# Relay_Drivers.net
KiCad netlist of a schematic drawn in EAGLE
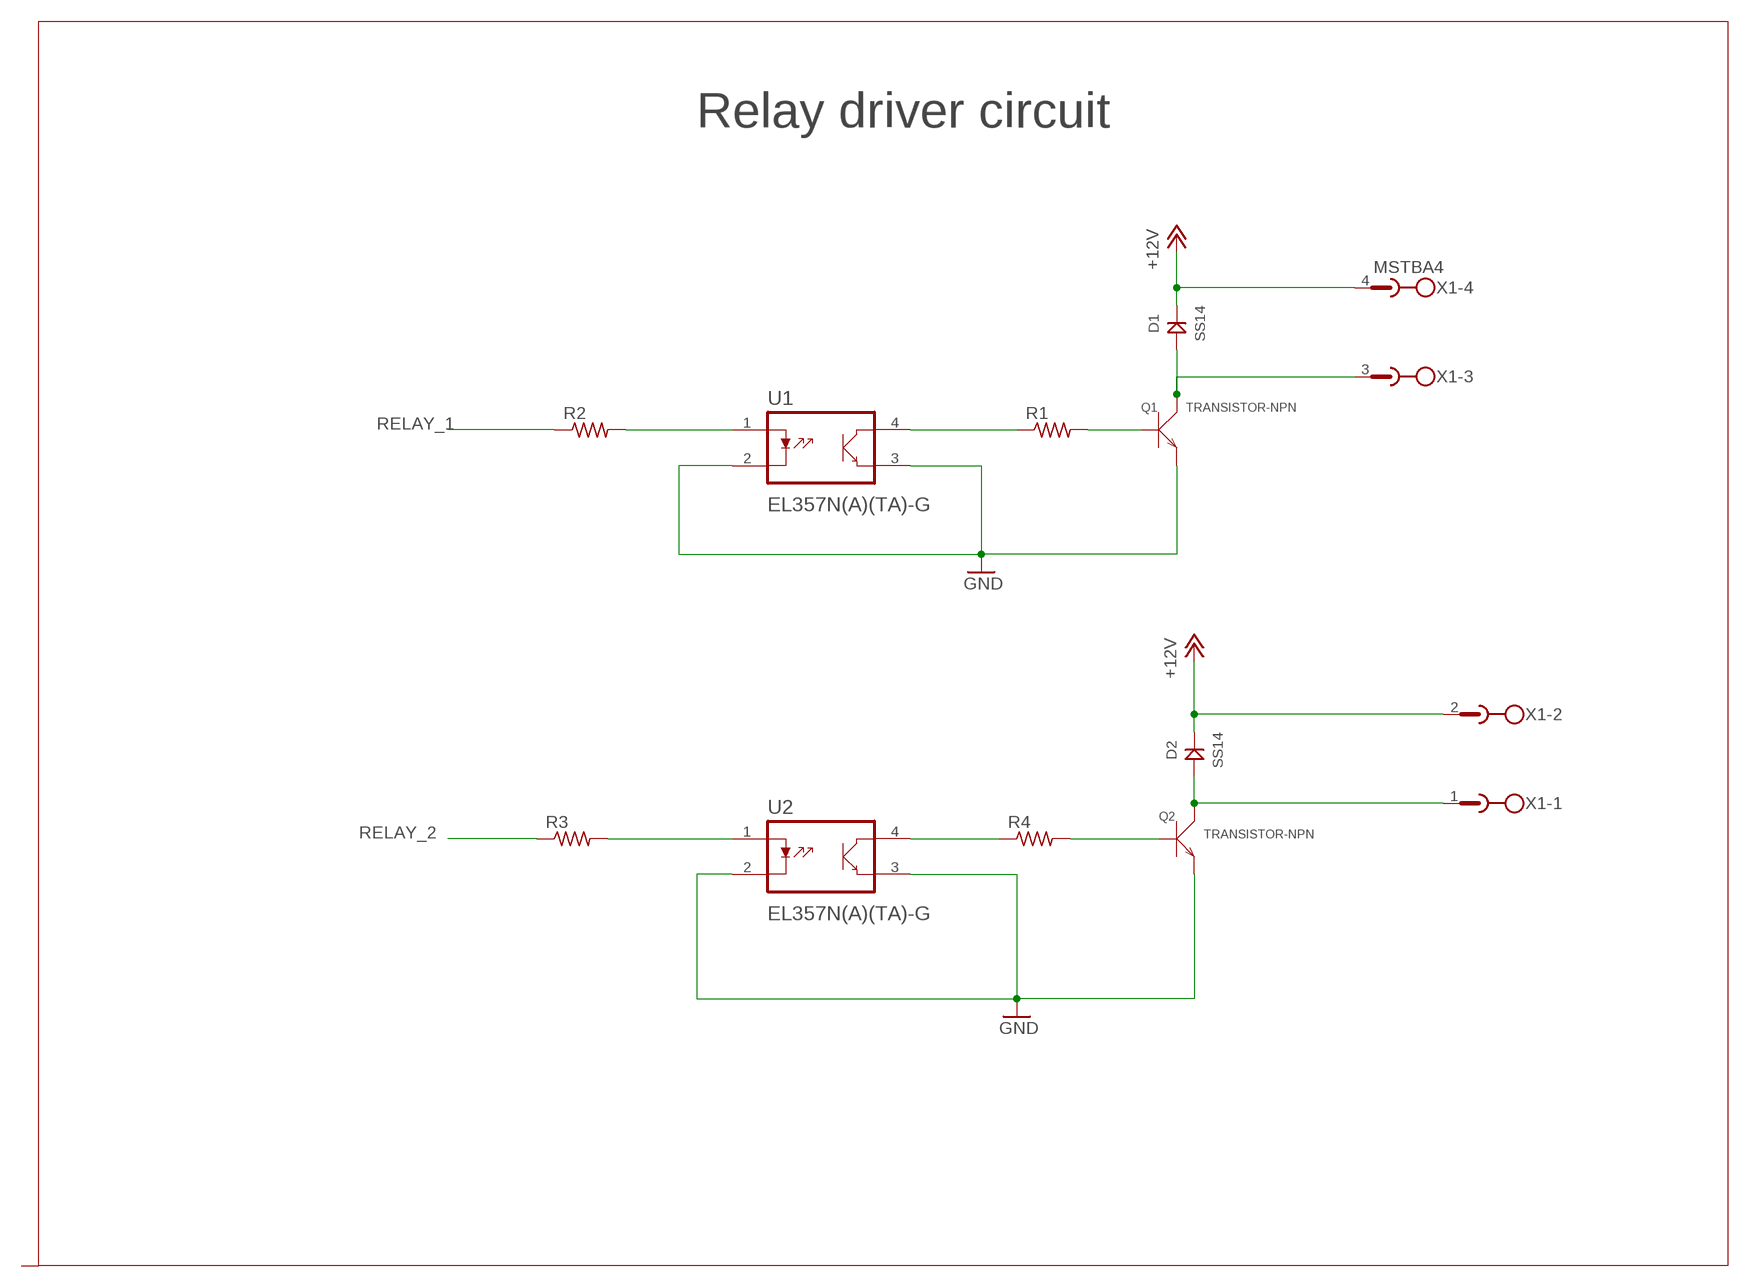
[diagram p0: schematic, sheet 1]

(export (version "E")
  (design (tool "Eeschema 10.0.6"))
  (components
    (comp (ref "D1")
      (value "SS14")
      (footprint "eagle-import:DO214")
      (fields (field (name "MF") "ON Semiconductor"))
      (libsource (lib "eagle-import") (part "SS14"))
    )
    (comp (ref "D2")
      (value "SS14")
      (footprint "eagle-import:DO214")
      (fields (field (name "MF") "ON Semiconductor"))
      (libsource (lib "eagle-import") (part "SS14"))
    )
    (comp (ref "Q1")
      (value "TRANSISTOR-NPN")
      (footprint "eagle-import:SOT-23")
      (fields (field (name "MF") "STMicroelectronics") (field (name "MP") "BC817-40"))
      (libsource (lib "eagle-import") (part "TRANSISTOR-NPN"))
    )
    (comp (ref "Q2")
      (value "TRANSISTOR-NPN")
      (footprint "eagle-import:SOT-23")
      (fields (field (name "MF") "STMicroelectronics") (field (name "MP") "BC817-40"))
      (libsource (lib "eagle-import") (part "TRANSISTOR-NPN"))
    )
    (comp (ref "R1")
      (value "R-US_R0805")
      (footprint "eagle-import:R0805")
      (libsource (lib "eagle-import") (part "R-US_R0805"))
    )
    (comp (ref "R2")
      (value "R-US_R0805")
      (footprint "eagle-import:R0805")
      (libsource (lib "eagle-import") (part "R-US_R0805"))
    )
    (comp (ref "R3")
      (value "R-US_R0805")
      (footprint "eagle-import:R0805")
      (libsource (lib "eagle-import") (part "R-US_R0805"))
    )
    (comp (ref "R4")
      (value "R-US_R0805")
      (footprint "eagle-import:R0805")
      (libsource (lib "eagle-import") (part "R-US_R0805"))
    )
    (comp (ref "U1")
      (value "EL357N(A)(TA)-G")
      (footprint "eagle-import:SOP254P700X200-4N")
      (fields (field (name "MF") "Everlight") (field (name "MP") "EL357N_A__TA_-G"))
      (libsource (lib "eagle-import") (part "EL357N(A)(TA)-G"))
    )
    (comp (ref "U2")
      (value "EL357N(A)(TA)-G")
      (footprint "eagle-import:SOP254P700X200-4N")
      (fields (field (name "MF") "Everlight") (field (name "MP") "EL357N_A__TA_-G"))
      (libsource (lib "eagle-import") (part "EL357N(A)(TA)-G"))
    )
    (comp (ref "X1")
      (value "MSTBA4")
      (footprint "eagle-import:MSTBA4")
      (fields (field (name "MF") "FARNELL") (field (name "MPN") "1757268"))
      (libsource (lib "eagle-import") (part "MSTBA4"))
    )
  )
  (nets
    (net (code "1") (name "+12V") (class "Default")
      (node (ref "D1") (pin "CATHODE") (pinfunction "KATHODE_CATHODE") (pintype "bidirectional"))
      (node (ref "D2") (pin "CATHODE") (pinfunction "KATHODE_CATHODE") (pintype "bidirectional"))
      (node (ref "X1") (pin "2") (pinfunction "1_2") (pintype "passive"))
      (node (ref "X1") (pin "4") (pinfunction "1_4") (pintype "passive"))
    )
    (net (code "2") (name "/RELAY_1") (class "Default")
      (node (ref "R2") (pin "1") (pinfunction "1_1") (pintype "passive"))
    )
    (net (code "3") (name "/RELAY_2") (class "Default")
      (node (ref "R3") (pin "1") (pinfunction "1_1") (pintype "passive"))
    )
    (net (code "4") (name "GND") (class "Default")
      (node (ref "Q1") (pin "2") (pinfunction "E_2") (pintype "passive"))
      (node (ref "Q2") (pin "2") (pinfunction "E_2") (pintype "passive"))
      (node (ref "U1") (pin "2") (pinfunction "K_2") (pintype "passive"))
      (node (ref "U1") (pin "3") (pinfunction "E_3") (pintype "passive"))
      (node (ref "U2") (pin "2") (pinfunction "K_2") (pintype "passive"))
      (node (ref "U2") (pin "3") (pinfunction "E_3") (pintype "passive"))
    )
    (net (code "5") (name "Net-(Q1-B)") (class "Default")
      (node (ref "Q1") (pin "1") (pinfunction "B_1") (pintype "passive"))
      (node (ref "R1") (pin "2") (pinfunction "2_2") (pintype "passive"))
    )
    (net (code "6") (name "Net-(Q1-C)") (class "Default")
      (node (ref "D1") (pin "ANODE") (pinfunction "ANODE_ANODE") (pintype "bidirectional"))
      (node (ref "Q1") (pin "3") (pinfunction "C_3") (pintype "passive"))
      (node (ref "X1") (pin "3") (pinfunction "1_3") (pintype "passive"))
    )
    (net (code "7") (name "Net-(Q2-B)") (class "Default")
      (node (ref "Q2") (pin "1") (pinfunction "B_1") (pintype "passive"))
      (node (ref "R4") (pin "2") (pinfunction "2_2") (pintype "passive"))
    )
    (net (code "8") (name "Net-(Q2-C)") (class "Default")
      (node (ref "D2") (pin "ANODE") (pinfunction "ANODE_ANODE") (pintype "bidirectional"))
      (node (ref "Q2") (pin "3") (pinfunction "C_3") (pintype "passive"))
      (node (ref "X1") (pin "1") (pinfunction "1_1") (pintype "passive"))
    )
    (net (code "9") (name "Net-(U1-A)") (class "Default")
      (node (ref "R2") (pin "2") (pinfunction "2_2") (pintype "passive"))
      (node (ref "U1") (pin "1") (pinfunction "A_1") (pintype "passive"))
    )
    (net (code "10") (name "Net-(U1-C)") (class "Default")
      (node (ref "R1") (pin "1") (pinfunction "1_1") (pintype "passive"))
      (node (ref "U1") (pin "4") (pinfunction "C_4") (pintype "passive"))
    )
    (net (code "11") (name "Net-(U2-A)") (class "Default")
      (node (ref "R3") (pin "2") (pinfunction "2_2") (pintype "passive"))
      (node (ref "U2") (pin "1") (pinfunction "A_1") (pintype "passive"))
    )
    (net (code "12") (name "Net-(U2-C)") (class "Default")
      (node (ref "R4") (pin "1") (pinfunction "1_1") (pintype "passive"))
      (node (ref "U2") (pin "4") (pinfunction "C_4") (pintype "passive"))
    )
  )
)
